# 1-Schematic_TL071-dop.net
KiCad netlist of a schematic drawn in EasyEDA
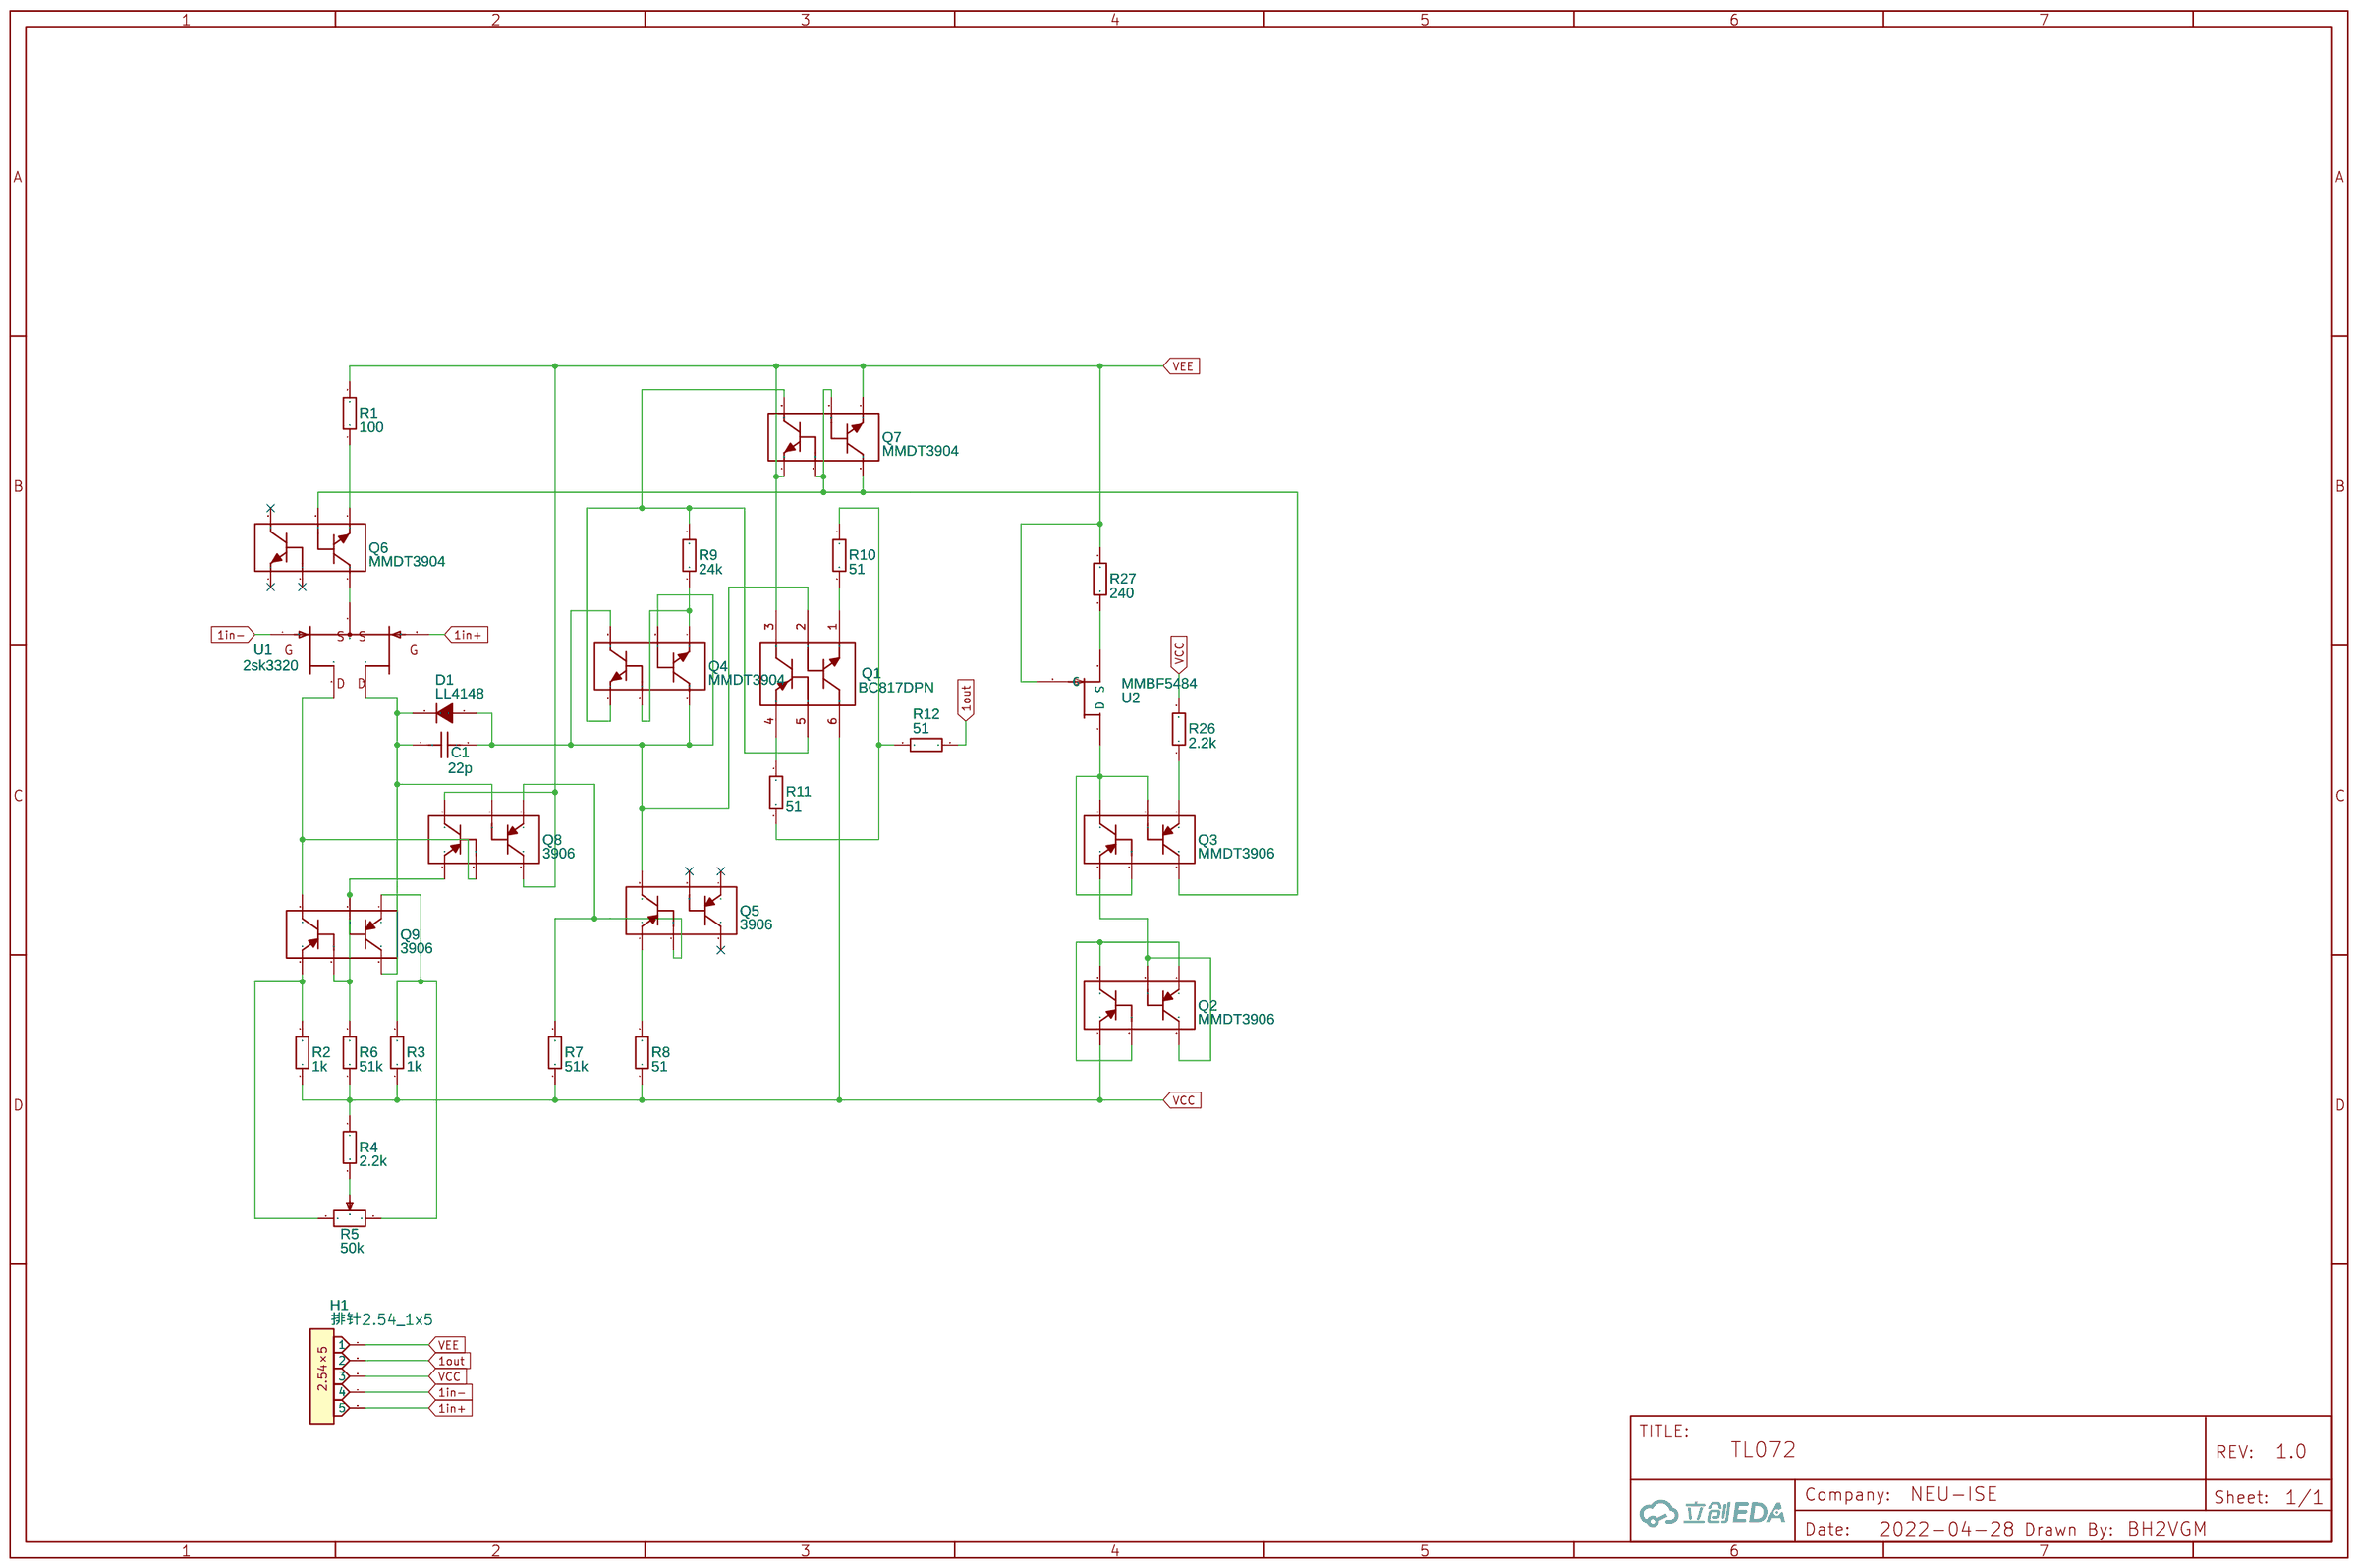
[diagram p0: schematic sheet]

(export (version "E")
  (design (tool "Eeschema 10.0.6"))
  (components
    (comp (ref "C1")
      (value "22p")
      (fields
        (field (name "BOM_Manufacturer Part") "C0805X7R103J500NT")
        (field (name "BOM_Supplier Part") "C2835540")
      )
      (libsource (lib "") (part "C0805X7R103J500NT"))
    )
    (comp (ref "D1")
      (value "LL4148")
      (fields
        (field (name "BOM_Manufacturer Part") "LL4148-GS08")
        (field (name "BOM_Supplier Part") "C68883")
      )
      (libsource (lib "") (part "LL4148"))
    )
    (comp (ref "H1")
      (value "排针2.54_1x5")
      (fields
        (field (name "BOM_Manufacturer Part") "MTP125-1105S1")
        (field (name "BOM_Supplier Part") "C358687")
      )
      (libsource (lib "") (part "排针2.54_1x5"))
    )
    (comp (ref "Q1")
      (value "BC817DPN")
      (fields
        (field (name "BOM_Manufacturer Part") "BC817DPN_R1_00001")
        (field (name "BOM_Supplier Part") "C696397")
      )
      (libsource (lib "") (part "BC817DPN_R1_00001"))
    )
    (comp (ref "Q2")
      (value "MMDT3906")
      (fields
        (field (name "BOM_Manufacturer Part") "MMDT3906-TP")
        (field (name "BOM_Supplier Part") "C779248")
      )
      (libsource (lib "") (part "MMDT3906"))
    )
    (comp (ref "Q3")
      (value "MMDT3906")
      (fields
        (field (name "BOM_Manufacturer Part") "MMDT3906-TP")
        (field (name "BOM_Supplier Part") "C779248")
      )
      (libsource (lib "") (part "MMDT3906"))
    )
    (comp (ref "Q4")
      (value "MMDT3904")
      (fields
        (field (name "BOM_Manufacturer Part") "MMDT3904-7-F")
        (field (name "BOM_Supplier Part") "C83572")
      )
      (libsource (lib "") (part "MMDT3904"))
    )
    (comp (ref "Q5")
      (value "3906")
      (fields
        (field (name "BOM_Manufacturer Part") "MMDT3906-TP")
        (field (name "BOM_Supplier Part") "C779248")
      )
      (libsource (lib "") (part "MMDT3906"))
    )
    (comp (ref "Q6")
      (value "MMDT3904")
      (fields
        (field (name "BOM_Manufacturer Part") "MMDT3904-7-F")
        (field (name "BOM_Supplier Part") "C83572")
      )
      (libsource (lib "") (part "MMDT3904"))
    )
    (comp (ref "Q7")
      (value "MMDT3904")
      (fields
        (field (name "BOM_Manufacturer Part") "MMDT3904-7-F")
        (field (name "BOM_Supplier Part") "C83572")
      )
      (libsource (lib "") (part "MMDT3904"))
    )
    (comp (ref "Q8")
      (value "3906")
      (fields
        (field (name "BOM_Manufacturer Part") "MMDT3906-TP")
        (field (name "BOM_Supplier Part") "C779248")
      )
      (libsource (lib "") (part "MMDT3906"))
    )
    (comp (ref "Q9")
      (value "3906")
      (fields
        (field (name "BOM_Manufacturer Part") "MMDT3906-TP")
        (field (name "BOM_Supplier Part") "C779248")
      )
      (libsource (lib "") (part "MMDT3906"))
    )
    (comp (ref "R1")
      (value "100")
      (fields (field (name "BOM_Manufacturer Part") "0805") (field (name "BOM_Supplier Part") "C9900012715"))
      (libsource (lib "") (part "0805"))
    )
    (comp (ref "R2")
      (value "1k")
      (fields (field (name "BOM_Manufacturer Part") "0805") (field (name "BOM_Supplier Part") "C9900012715"))
      (libsource (lib "") (part "0805"))
    )
    (comp (ref "R3")
      (value "1k")
      (fields (field (name "BOM_Manufacturer Part") "0805") (field (name "BOM_Supplier Part") "C9900012715"))
      (libsource (lib "") (part "0805"))
    )
    (comp (ref "R4")
      (value "2.2k")
      (fields (field (name "BOM_Manufacturer Part") "0805") (field (name "BOM_Supplier Part") "C9900012715"))
      (libsource (lib "") (part "0805_1"))
    )
    (comp (ref "R5")
      (value "50k")
      (fields
        (field (name "BOM_Manufacturer Part") "3296W-1-103LF")
        (field (name "BOM_Supplier Part") "C34846")
      )
      (libsource (lib "") (part "3296W"))
    )
    (comp (ref "R6")
      (value "51k")
      (fields (field (name "BOM_Manufacturer Part") "0805") (field (name "BOM_Supplier Part") "C9900012715"))
      (libsource (lib "") (part "0805"))
    )
    (comp (ref "R7")
      (value "51k")
      (fields (field (name "BOM_Manufacturer Part") "0805") (field (name "BOM_Supplier Part") "C9900012715"))
      (libsource (lib "") (part "0805"))
    )
    (comp (ref "R8")
      (value "51")
      (fields (field (name "BOM_Manufacturer Part") "0805") (field (name "BOM_Supplier Part") "C9900012715"))
      (libsource (lib "") (part "0805"))
    )
    (comp (ref "R9")
      (value "24k")
      (fields (field (name "BOM_Manufacturer Part") "0805") (field (name "BOM_Supplier Part") "C9900012715"))
      (libsource (lib "") (part "0805"))
    )
    (comp (ref "R10")
      (value "51")
      (fields (field (name "BOM_Manufacturer Part") "0805") (field (name "BOM_Supplier Part") "C9900012715"))
      (libsource (lib "") (part "0805_1"))
    )
    (comp (ref "R11")
      (value "51")
      (fields (field (name "BOM_Manufacturer Part") "0805") (field (name "BOM_Supplier Part") "C9900012715"))
      (libsource (lib "") (part "0805_1"))
    )
    (comp (ref "R12")
      (value "51")
      (fields (field (name "BOM_Manufacturer Part") "0805") (field (name "BOM_Supplier Part") "C9900012715"))
      (libsource (lib "") (part "0805_2"))
    )
    (comp (ref "R26")
      (value "2.2k")
      (fields (field (name "BOM_Manufacturer Part") "0805") (field (name "BOM_Supplier Part") "C9900012715"))
      (libsource (lib "") (part "0805"))
    )
    (comp (ref "R27")
      (value "240")
      (fields (field (name "BOM_Manufacturer Part") "0805") (field (name "BOM_Supplier Part") "C9900012715"))
      (libsource (lib "") (part "0805_1"))
    )
    (comp (ref "U1") (value "2sk3320") (libsource (lib "") (part "2sk3320")))
    (comp (ref "U2")
      (value "MMBF5484")
      (fields (field (name "BOM_Supplier Part") "C274687"))
      (libsource (lib "") (part "MMBF5484"))
    )
  )
  (nets
    (net (code "1") (name "1in+") (class "Default")
      (node (ref "H1") (pin "5") (pinfunction "5_5") (pintype "unspecified"))
      (node (ref "U1") (pin "5") (pinfunction "G_5") (pintype "unspecified"))
    )
    (net (code "2") (name "1in-") (class "Default")
      (node (ref "H1") (pin "4") (pinfunction "4_4") (pintype "unspecified"))
      (node (ref "U1") (pin "4") (pinfunction "G_4") (pintype "unspecified"))
    )
    (net (code "3") (name "1out") (class "Default")
      (node (ref "H1") (pin "2") (pinfunction "2_2") (pintype "unspecified"))
      (node (ref "R12") (pin "1") (pinfunction "1_1") (pintype "unspecified"))
    )
    (net (code "4") (name "Net-(D1-A)") (class "Default")
      (node (ref "C1") (pin "2") (pinfunction "2_2") (pintype "unspecified"))
      (node (ref "D1") (pin "2") (pinfunction "A_2") (pintype "unspecified"))
      (node (ref "Q1") (pin "2") (pinfunction "B1_2") (pintype "unspecified"))
      (node (ref "Q4") (pin "3") (pinfunction "C_3") (pintype "unspecified"))
      (node (ref "Q4") (pin "5") (pinfunction "B_5") (pintype "unspecified"))
      (node (ref "Q4") (pin "6") (pinfunction "C_6") (pintype "unspecified"))
      (node (ref "Q5") (pin "6") (pinfunction "C_6") (pintype "unspecified"))
    )
    (net (code "5") (name "Net-(D1-C)") (class "Default")
      (node (ref "C1") (pin "1") (pinfunction "1_1") (pintype "unspecified"))
      (node (ref "D1") (pin "1") (pinfunction "C_1") (pintype "unspecified"))
      (node (ref "Q8") (pin "5") (pinfunction "B_5") (pintype "unspecified"))
      (node (ref "Q9") (pin "3") (pinfunction "C_3") (pintype "unspecified"))
      (node (ref "U1") (pin "1") (pinfunction "D_1") (pintype "unspecified"))
    )
    (net (code "6") (name "Net-(Q1-B2)") (class "Default")
      (node (ref "Q1") (pin "5") (pinfunction "B2_5") (pintype "unspecified"))
      (node (ref "Q4") (pin "1") (pinfunction "E_1") (pintype "unspecified"))
      (node (ref "Q7") (pin "6") (pinfunction "C_6") (pintype "unspecified"))
      (node (ref "R9") (pin "2") (pinfunction "2_2") (pintype "unspecified"))
    )
    (net (code "7") (name "Net-(Q1-E1)") (class "Default")
      (node (ref "Q1") (pin "1") (pinfunction "E1_1") (pintype "unspecified"))
      (node (ref "R10") (pin "2") (pinfunction "2_2") (pintype "unspecified"))
    )
    (net (code "8") (name "Net-(Q1-E2)") (class "Default")
      (node (ref "Q1") (pin "4") (pinfunction "E2_4") (pintype "unspecified"))
      (node (ref "R11") (pin "1") (pinfunction "1_1") (pintype "unspecified"))
    )
    (net (code "9") (name "Net-(Q2-B-Pad2)") (class "Default")
      (node (ref "Q2") (pin "2") (pinfunction "B_2") (pintype "unspecified"))
      (node (ref "Q2") (pin "4") (pinfunction "E_4") (pintype "unspecified"))
      (node (ref "Q2") (pin "6") (pinfunction "C_6") (pintype "unspecified"))
    )
    (net (code "10") (name "Net-(Q2-B-Pad5)") (class "Default")
      (node (ref "Q2") (pin "3") (pinfunction "C_3") (pintype "unspecified"))
      (node (ref "Q2") (pin "5") (pinfunction "B_5") (pintype "unspecified"))
      (node (ref "Q3") (pin "1") (pinfunction "E_1") (pintype "unspecified"))
    )
    (net (code "11") (name "Net-(Q3-C-Pad3)") (class "Default")
      (node (ref "Q3") (pin "3") (pinfunction "C_3") (pintype "unspecified"))
      (node (ref "Q6") (pin "5") (pinfunction "B_5") (pintype "unspecified"))
      (node (ref "Q7") (pin "2") (pinfunction "B_2") (pintype "unspecified"))
      (node (ref "Q7") (pin "3") (pinfunction "C_3") (pintype "unspecified"))
      (node (ref "Q7") (pin "5") (pinfunction "B_5") (pintype "unspecified"))
    )
    (net (code "12") (name "Net-(Q3-E-Pad4)") (class "Default")
      (node (ref "Q3") (pin "4") (pinfunction "E_4") (pintype "unspecified"))
      (node (ref "R26") (pin "1") (pinfunction "1_1") (pintype "unspecified"))
    )
    (net (code "13") (name "Net-(Q4-B-Pad2)") (class "Default")
      (node (ref "Q4") (pin "2") (pinfunction "B_2") (pintype "unspecified"))
      (node (ref "Q4") (pin "4") (pinfunction "E_4") (pintype "unspecified"))
      (node (ref "R9") (pin "1") (pinfunction "1_1") (pintype "unspecified"))
    )
    (net (code "14") (name "Net-(Q5-B-Pad2)") (class "Default")
      (node (ref "Q5") (pin "2") (pinfunction "B_2") (pintype "unspecified"))
      (node (ref "Q8") (pin "4") (pinfunction "E_4") (pintype "unspecified"))
      (node (ref "R7") (pin "2") (pinfunction "2_2") (pintype "unspecified"))
    )
    (net (code "15") (name "Net-(Q5-E-Pad1)") (class "Default")
      (node (ref "Q5") (pin "1") (pinfunction "E_1") (pintype "unspecified"))
      (node (ref "R8") (pin "2") (pinfunction "2_2") (pintype "unspecified"))
    )
    (net (code "16") (name "Net-(Q6-E-Pad4)") (class "Default")
      (node (ref "Q6") (pin "4") (pinfunction "E_4") (pintype "unspecified"))
      (node (ref "R1") (pin "1") (pinfunction "1_1") (pintype "unspecified"))
    )
    (net (code "17") (name "Net-(Q8-B-Pad2)") (class "Default")
      (node (ref "Q8") (pin "2") (pinfunction "B_2") (pintype "unspecified"))
      (node (ref "Q9") (pin "6") (pinfunction "C_6") (pintype "unspecified"))
      (node (ref "U1") (pin "3") (pinfunction "D_3") (pintype "unspecified"))
    )
    (net (code "18") (name "Net-(Q8-E-Pad1)") (class "Default")
      (node (ref "Q8") (pin "1") (pinfunction "E_1") (pintype "unspecified"))
      (node (ref "Q9") (pin "2") (pinfunction "B_2") (pintype "unspecified"))
      (node (ref "Q9") (pin "5") (pinfunction "B_5") (pintype "unspecified"))
      (node (ref "R6") (pin "2") (pinfunction "2_2") (pintype "unspecified"))
    )
    (net (code "19") (name "Net-(Q9-E-Pad1)") (class "Default")
      (node (ref "Q9") (pin "1") (pinfunction "E_1") (pintype "unspecified"))
      (node (ref "R2") (pin "2") (pinfunction "2_2") (pintype "unspecified"))
      (node (ref "R5") (pin "3") (pinfunction "3_3") (pintype "input"))
    )
    (net (code "20") (name "Net-(Q9-E-Pad4)") (class "Default")
      (node (ref "Q9") (pin "4") (pinfunction "E_4") (pintype "unspecified"))
      (node (ref "R3") (pin "2") (pinfunction "2_2") (pintype "unspecified"))
      (node (ref "R5") (pin "1") (pinfunction "1_1") (pintype "input"))
    )
    (net (code "21") (name "Net-(R4-Pad2)") (class "Default")
      (node (ref "R4") (pin "2") (pinfunction "2_2") (pintype "unspecified"))
      (node (ref "R5") (pin "2") (pinfunction "2_2") (pintype "input"))
    )
    (net (code "22") (name "Net-(R10-Pad1)") (class "Default")
      (node (ref "R10") (pin "1") (pinfunction "1_1") (pintype "unspecified"))
      (node (ref "R11") (pin "2") (pinfunction "2_2") (pintype "unspecified"))
      (node (ref "R12") (pin "2") (pinfunction "2_2") (pintype "unspecified"))
    )
    (net (code "23") (name "Net-(U1-S)") (class "Default")
      (node (ref "Q6") (pin "3") (pinfunction "C_3") (pintype "unspecified"))
      (node (ref "U1") (pin "2") (pinfunction "S_2") (pintype "unspecified"))
    )
    (net (code "24") (name "Net-(U2-D)") (class "Default")
      (node (ref "Q3") (pin "2") (pinfunction "B_2") (pintype "unspecified"))
      (node (ref "Q3") (pin "5") (pinfunction "B_5") (pintype "unspecified"))
      (node (ref "Q3") (pin "6") (pinfunction "C_6") (pintype "unspecified"))
      (node (ref "U2") (pin "1") (pinfunction "D_1") (pintype "unspecified"))
    )
    (net (code "25") (name "Net-(U2-S)") (class "Default")
      (node (ref "R27") (pin "2") (pinfunction "2_2") (pintype "unspecified"))
      (node (ref "U2") (pin "2") (pinfunction "S_2") (pintype "unspecified"))
    )
    (net (code "26") (name "VCC") (class "Default")
      (node (ref "H1") (pin "3") (pinfunction "3_3") (pintype "unspecified"))
      (node (ref "Q1") (pin "6") (pinfunction "C1_6") (pintype "unspecified"))
      (node (ref "Q2") (pin "1") (pinfunction "E_1") (pintype "unspecified"))
      (node (ref "R2") (pin "1") (pinfunction "1_1") (pintype "unspecified"))
      (node (ref "R26") (pin "2") (pinfunction "2_2") (pintype "unspecified"))
      (node (ref "R3") (pin "1") (pinfunction "1_1") (pintype "unspecified"))
      (node (ref "R4") (pin "1") (pinfunction "1_1") (pintype "unspecified"))
      (node (ref "R6") (pin "1") (pinfunction "1_1") (pintype "unspecified"))
      (node (ref "R7") (pin "1") (pinfunction "1_1") (pintype "unspecified"))
      (node (ref "R8") (pin "1") (pinfunction "1_1") (pintype "unspecified"))
    )
    (net (code "27") (name "VEE") (class "Default")
      (node (ref "H1") (pin "1") (pinfunction "1_1") (pintype "unspecified"))
      (node (ref "Q1") (pin "3") (pinfunction "C2_3") (pintype "unspecified"))
      (node (ref "Q7") (pin "1") (pinfunction "E_1") (pintype "unspecified"))
      (node (ref "Q7") (pin "4") (pinfunction "E_4") (pintype "unspecified"))
      (node (ref "Q8") (pin "3") (pinfunction "C_3") (pintype "unspecified"))
      (node (ref "Q8") (pin "6") (pinfunction "C_6") (pintype "unspecified"))
      (node (ref "R1") (pin "2") (pinfunction "2_2") (pintype "unspecified"))
      (node (ref "R27") (pin "1") (pinfunction "1_1") (pintype "unspecified"))
      (node (ref "U2") (pin "3") (pinfunction "G_3") (pintype "unspecified"))
    )
    (net (code "28") (name "unconnected-(Q5-B-Pad5)") (class "Default")
      (node (ref "Q5") (pin "5") (pinfunction "B_5") (pintype "unspecified+no_connect"))
    )
    (net (code "29") (name "unconnected-(Q5-C-Pad3)") (class "Default")
      (node (ref "Q5") (pin "3") (pinfunction "C_3") (pintype "unspecified+no_connect"))
    )
    (net (code "30") (name "unconnected-(Q5-E-Pad4)") (class "Default")
      (node (ref "Q5") (pin "4") (pinfunction "E_4") (pintype "unspecified+no_connect"))
    )
    (net (code "31") (name "unconnected-(Q6-B-Pad2)") (class "Default")
      (node (ref "Q6") (pin "2") (pinfunction "B_2") (pintype "unspecified+no_connect"))
    )
    (net (code "32") (name "unconnected-(Q6-C-Pad6)") (class "Default")
      (node (ref "Q6") (pin "6") (pinfunction "C_6") (pintype "unspecified+no_connect"))
    )
    (net (code "33") (name "unconnected-(Q6-E-Pad1)") (class "Default")
      (node (ref "Q6") (pin "1") (pinfunction "E_1") (pintype "unspecified+no_connect"))
    )
  )
)
